# Power_Distro_Board_V5.net
KiCad netlist of a schematic drawn in EAGLE
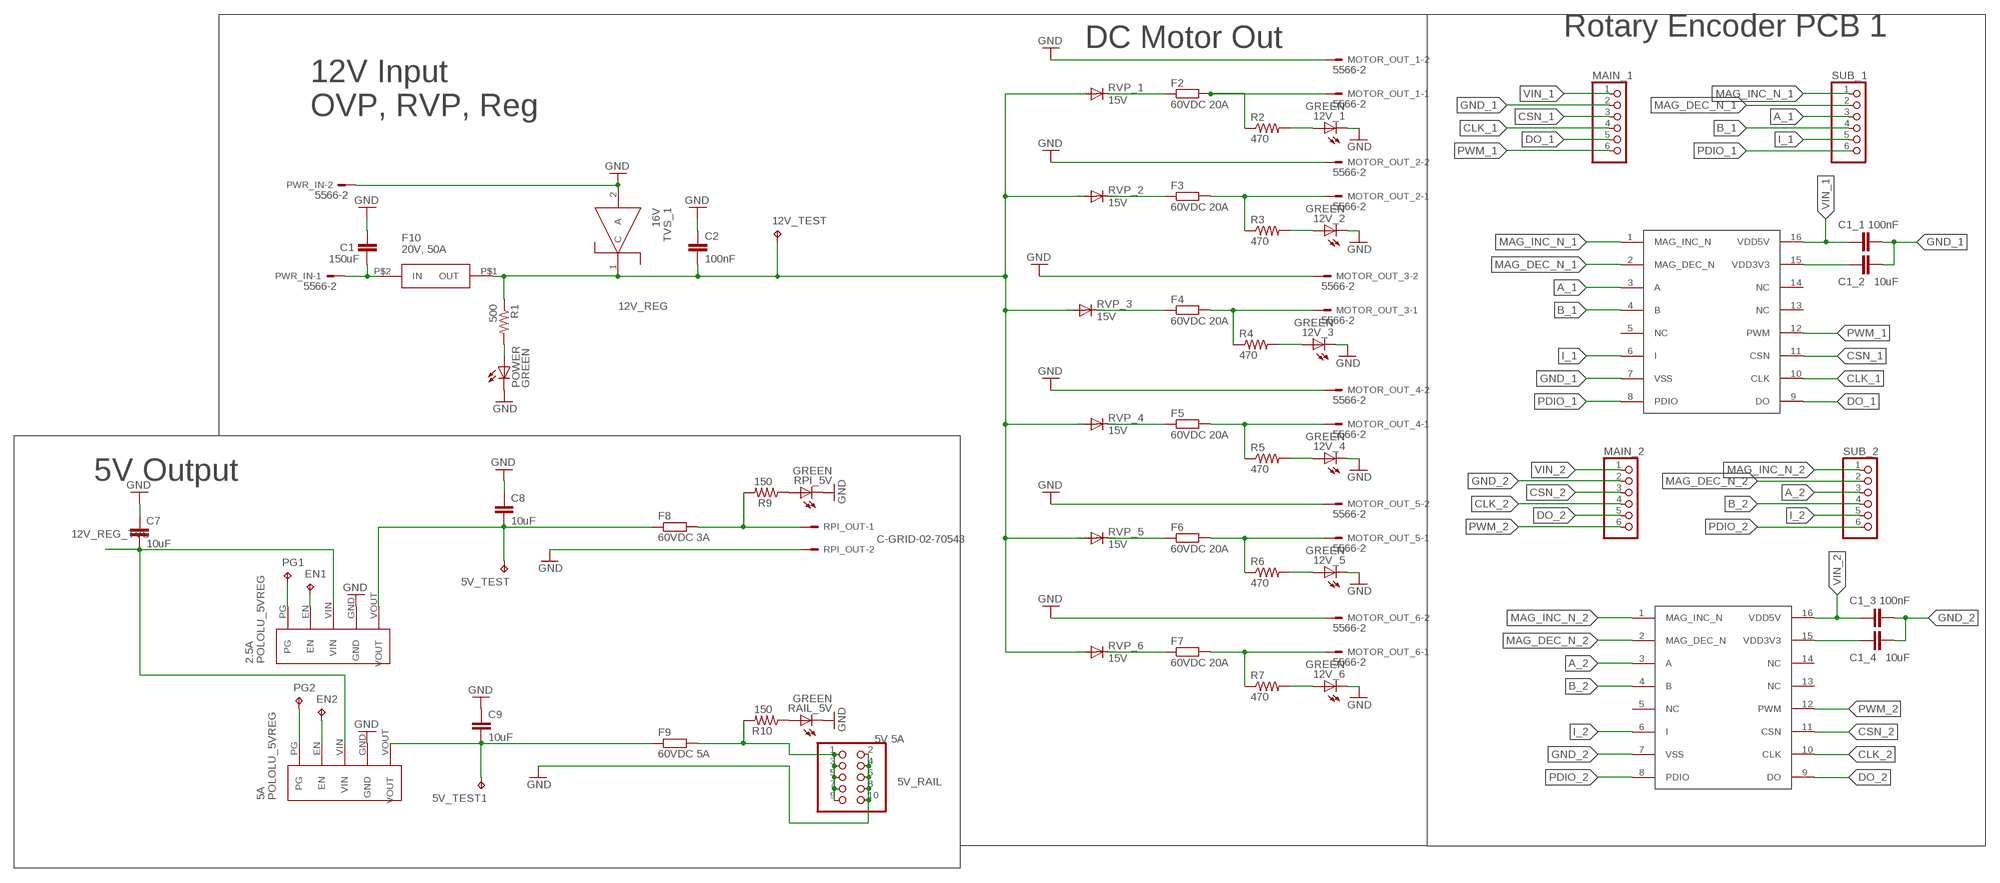
[diagram p0: schematic, sheet 1]

(export (version "E")
  (design (tool "Eeschema 10.0.6"))
  (components
    (comp (ref "2.5A")
      (value "POLOLU_5VREG")
      (footprint "eagle-import:SIP5")
      (libsource (lib "eagle-import") (part "POLOLU_5VREG"))
    )
    (comp (ref "5A")
      (value "POLOLU_5VREG")
      (footprint "eagle-import:SIP5")
      (libsource (lib "eagle-import") (part "POLOLU_5VREG"))
    )
    (comp (ref "5V_RAIL")
      (value "5V 5A")
      (footprint "eagle-import:2X05")
      (libsource (lib "eagle-import") (part "PINHD-2X5"))
    )
    (comp (ref "5V_TEST")
      (value "TPPAD1-13")
      (footprint "eagle-import:P1-13")
      (libsource (lib "eagle-import") (part "TPPAD1-13"))
    )
    (comp (ref "5V_TEST1")
      (value "TPPAD1-13")
      (footprint "eagle-import:P1-13")
      (libsource (lib "eagle-import") (part "TPPAD1-13"))
    )
    (comp (ref "12V_1")
      (value "GREEN")
      (footprint "eagle-import:SML1206")
      (libsource (lib "eagle-import") (part "LEDSML1206"))
    )
    (comp (ref "12V_2")
      (value "GREEN")
      (footprint "eagle-import:SML1206")
      (libsource (lib "eagle-import") (part "LEDSML1206"))
    )
    (comp (ref "12V_3")
      (value "GREEN")
      (footprint "eagle-import:SML1206")
      (libsource (lib "eagle-import") (part "LEDSML1206"))
    )
    (comp (ref "12V_4")
      (value "GREEN")
      (footprint "eagle-import:SML1206")
      (libsource (lib "eagle-import") (part "LEDSML1206"))
    )
    (comp (ref "12V_5")
      (value "GREEN")
      (footprint "eagle-import:SML1206")
      (libsource (lib "eagle-import") (part "LEDSML1206"))
    )
    (comp (ref "12V_6")
      (value "GREEN")
      (footprint "eagle-import:SML1206")
      (libsource (lib "eagle-import") (part "LEDSML1206"))
    )
    (comp (ref "12V_TEST")
      (value "TPPAD1-13")
      (footprint "eagle-import:P1-13")
      (libsource (lib "eagle-import") (part "TPPAD1-13"))
    )
    (comp (ref "C1")
      (value "150uF")
      (footprint "eagle-import:C1206")
      (libsource (lib "eagle-import") (part "C-EUC1206"))
    )
    (comp (ref "C1_1")
      (value "100nF")
      (footprint "eagle-import:C1206")
      (libsource (lib "eagle-import") (part "C-EUC1206"))
    )
    (comp (ref "C1_2")
      (value "10uF")
      (footprint "eagle-import:C1206")
      (libsource (lib "eagle-import") (part "C-EUC1206"))
    )
    (comp (ref "C1_3")
      (value "100nF")
      (footprint "eagle-import:C1206")
      (libsource (lib "eagle-import") (part "C-EUC1206"))
    )
    (comp (ref "C1_4")
      (value "10uF")
      (footprint "eagle-import:C1206")
      (libsource (lib "eagle-import") (part "C-EUC1206"))
    )
    (comp (ref "C2")
      (value "100nF")
      (footprint "eagle-import:C1206")
      (libsource (lib "eagle-import") (part "C-EUC1206"))
    )
    (comp (ref "C7")
      (value "10uF")
      (footprint "eagle-import:C1206")
      (libsource (lib "eagle-import") (part "C-EUC1206"))
    )
    (comp (ref "C8")
      (value "10uF")
      (footprint "eagle-import:C1206")
      (libsource (lib "eagle-import") (part "C-EUC1206"))
    )
    (comp (ref "C9")
      (value "10uF")
      (footprint "eagle-import:C1206")
      (libsource (lib "eagle-import") (part "C-EUC1206"))
    )
    (comp (ref "EN1")
      (value "TPPAD1-13")
      (footprint "eagle-import:P1-13")
      (libsource (lib "eagle-import") (part "TPPAD1-13"))
    )
    (comp (ref "EN2")
      (value "TPPAD1-13")
      (footprint "eagle-import:P1-13")
      (libsource (lib "eagle-import") (part "TPPAD1-13"))
    )
    (comp (ref "ENC_1")
      (value "ENCODER_AS5045B")
      (footprint "eagle-import:SSOP16")
      (libsource (lib "eagle-import") (part "ENCODER_AS5045B"))
    )
    (comp (ref "ENC_2")
      (value "ENCODER_AS5045B")
      (footprint "eagle-import:SSOP16")
      (libsource (lib "eagle-import") (part "ENCODER_AS5045B"))
    )
    (comp (ref "F2")
      (value "60VDC 20A")
      (footprint "eagle-import:M1206")
      (libsource (lib "eagle-import") (part "R-EU_M1206"))
    )
    (comp (ref "F3")
      (value "60VDC 20A")
      (footprint "eagle-import:M1206")
      (libsource (lib "eagle-import") (part "R-EU_M1206"))
    )
    (comp (ref "F4")
      (value "60VDC 20A")
      (footprint "eagle-import:M1206")
      (libsource (lib "eagle-import") (part "R-EU_M1206"))
    )
    (comp (ref "F5")
      (value "60VDC 20A")
      (footprint "eagle-import:M1206")
      (libsource (lib "eagle-import") (part "R-EU_M1206"))
    )
    (comp (ref "F6")
      (value "60VDC 20A")
      (footprint "eagle-import:M1206")
      (libsource (lib "eagle-import") (part "R-EU_M1206"))
    )
    (comp (ref "F7")
      (value "60VDC 20A")
      (footprint "eagle-import:M1206")
      (libsource (lib "eagle-import") (part "R-EU_M1206"))
    )
    (comp (ref "F8")
      (value "60VDC 3A")
      (footprint "eagle-import:M1206")
      (libsource (lib "eagle-import") (part "R-EU_M1206"))
    )
    (comp (ref "F9")
      (value "60VDC 5A")
      (footprint "eagle-import:M1206")
      (libsource (lib "eagle-import") (part "R-EU_M1206"))
    )
    (comp (ref "F10")
      (value "20V, 50A")
      (footprint "eagle-import:NANO")
      (libsource (lib "eagle-import") (part "LITTLEFUSE_NANO"))
    )
    (comp (ref "MAIN_1")
      (value "PINHD-1X6")
      (footprint "eagle-import:1X06")
      (libsource (lib "eagle-import") (part "PINHD-1X6"))
    )
    (comp (ref "MAIN_2")
      (value "PINHD-1X6")
      (footprint "eagle-import:1X06")
      (libsource (lib "eagle-import") (part "PINHD-1X6"))
    )
    (comp (ref "MOTOR_OUT_1")
      (value "5566-2")
      (footprint "eagle-import:5566-2")
      (libsource (lib "eagle-import") (part "5566-2"))
    )
    (comp (ref "MOTOR_OUT_2")
      (value "5566-2")
      (footprint "eagle-import:5566-2")
      (libsource (lib "eagle-import") (part "5566-2"))
    )
    (comp (ref "MOTOR_OUT_3")
      (value "5566-2")
      (footprint "eagle-import:5566-2")
      (libsource (lib "eagle-import") (part "5566-2"))
    )
    (comp (ref "MOTOR_OUT_4")
      (value "5566-2")
      (footprint "eagle-import:5566-2")
      (libsource (lib "eagle-import") (part "5566-2"))
    )
    (comp (ref "MOTOR_OUT_5")
      (value "5566-2")
      (footprint "eagle-import:5566-2")
      (libsource (lib "eagle-import") (part "5566-2"))
    )
    (comp (ref "MOTOR_OUT_6")
      (value "5566-2")
      (footprint "eagle-import:5566-2")
      (libsource (lib "eagle-import") (part "5566-2"))
    )
    (comp (ref "PG1")
      (value "TPPAD1-13")
      (footprint "eagle-import:P1-13")
      (libsource (lib "eagle-import") (part "TPPAD1-13"))
    )
    (comp (ref "PG2")
      (value "TPPAD1-13")
      (footprint "eagle-import:P1-13")
      (libsource (lib "eagle-import") (part "TPPAD1-13"))
    )
    (comp (ref "POWER")
      (value "GREEN")
      (footprint "eagle-import:SML1206")
      (libsource (lib "eagle-import") (part "LEDSML1206"))
    )
    (comp (ref "PWR_IN")
      (value "5566-2")
      (footprint "eagle-import:5566-2")
      (libsource (lib "eagle-import") (part "5566-2"))
    )
    (comp (ref "R1")
      (value "500")
      (footprint "eagle-import:R1206")
      (libsource (lib "eagle-import") (part "R-US_R1206"))
    )
    (comp (ref "R2")
      (value "470")
      (footprint "eagle-import:R1206")
      (libsource (lib "eagle-import") (part "R-US_R1206"))
    )
    (comp (ref "R3")
      (value "470")
      (footprint "eagle-import:R1206")
      (libsource (lib "eagle-import") (part "R-US_R1206"))
    )
    (comp (ref "R4")
      (value "470")
      (footprint "eagle-import:R1206")
      (libsource (lib "eagle-import") (part "R-US_R1206"))
    )
    (comp (ref "R5")
      (value "470")
      (footprint "eagle-import:R1206")
      (libsource (lib "eagle-import") (part "R-US_R1206"))
    )
    (comp (ref "R6")
      (value "470")
      (footprint "eagle-import:R1206")
      (libsource (lib "eagle-import") (part "R-US_R1206"))
    )
    (comp (ref "R7")
      (value "470")
      (footprint "eagle-import:R1206")
      (libsource (lib "eagle-import") (part "R-US_R1206"))
    )
    (comp (ref "R9")
      (value "150")
      (footprint "eagle-import:R1206")
      (libsource (lib "eagle-import") (part "R-US_R1206"))
    )
    (comp (ref "R10")
      (value "150")
      (footprint "eagle-import:R1206")
      (libsource (lib "eagle-import") (part "R-US_R1206"))
    )
    (comp (ref "RAIL_5V")
      (value "GREEN")
      (footprint "eagle-import:SML1206")
      (libsource (lib "eagle-import") (part "LEDSML1206"))
    )
    (comp (ref "RPI_5V")
      (value "GREEN")
      (footprint "eagle-import:SML1206")
      (libsource (lib "eagle-import") (part "LEDSML1206"))
    )
    (comp (ref "RPI_OUT")
      (value "C-GRID-02-70543")
      (footprint "eagle-import:70543-02")
      (libsource (lib "eagle-import") (part "C-GRID-02-70543"))
    )
    (comp (ref "RVP_1")
      (value "15V")
      (footprint "eagle-import:TO220ACS")
      (libsource (lib "eagle-import") (part "BYT08P"))
    )
    (comp (ref "RVP_2")
      (value "15V")
      (footprint "eagle-import:TO220ACS")
      (libsource (lib "eagle-import") (part "BYT08P"))
    )
    (comp (ref "RVP_3")
      (value "15V")
      (footprint "eagle-import:TO220ACS")
      (libsource (lib "eagle-import") (part "BYT08P"))
    )
    (comp (ref "RVP_4")
      (value "15V")
      (footprint "eagle-import:TO220ACS")
      (libsource (lib "eagle-import") (part "BYT08P"))
    )
    (comp (ref "RVP_5")
      (value "15V")
      (footprint "eagle-import:TO220ACS")
      (libsource (lib "eagle-import") (part "BYT08P"))
    )
    (comp (ref "RVP_6")
      (value "15V")
      (footprint "eagle-import:TO220ACS")
      (libsource (lib "eagle-import") (part "BYT08P"))
    )
    (comp (ref "SUB_1")
      (value "PINHD-1X6")
      (footprint "eagle-import:1X06")
      (libsource (lib "eagle-import") (part "PINHD-1X6"))
    )
    (comp (ref "SUB_2")
      (value "PINHD-1X6")
      (footprint "eagle-import:1X06")
      (libsource (lib "eagle-import") (part "PINHD-1X6"))
    )
    (comp (ref "TVS_1")
      (value "16V")
      (footprint "eagle-import:DO-214AC")
      (libsource (lib "eagle-import") (part "SMAJ26A_TVSSMA"))
    )
  )
  (nets
    (net (code "1") (name "/12V_REG") (class "Default")
      (node (ref "12V_TEST") (pin "TP") (pinfunction "TP_TP") (pintype "input"))
      (node (ref "C2") (pin "2") (pinfunction "2_2") (pintype "passive"))
      (node (ref "F10") (pin "P$1") (pinfunction "OUT_P$1") (pintype "bidirectional"))
      (node (ref "R1") (pin "1") (pinfunction "1_1") (pintype "passive"))
      (node (ref "RVP_1") (pin "A") (pinfunction "A_A") (pintype "passive"))
      (node (ref "RVP_2") (pin "A") (pinfunction "A_A") (pintype "passive"))
      (node (ref "RVP_3") (pin "A") (pinfunction "A_A") (pintype "passive"))
      (node (ref "RVP_4") (pin "A") (pinfunction "A_A") (pintype "passive"))
      (node (ref "RVP_5") (pin "A") (pinfunction "A_A") (pintype "passive"))
      (node (ref "RVP_6") (pin "A") (pinfunction "A_A") (pintype "passive"))
      (node (ref "TVS_1") (pin "1") (pinfunction "C_1") (pintype "bidirectional"))
    )
    (net (code "2") (name "/12V_REG_TVS") (class "Default")
      (node (ref "2.5A") (pin "VIN") (pinfunction "VIN_VIN") (pintype "bidirectional"))
      (node (ref "5A") (pin "VIN") (pinfunction "VIN_VIN") (pintype "bidirectional"))
      (node (ref "C7") (pin "2") (pinfunction "2_2") (pintype "passive"))
    )
    (net (code "3") (name "A_1") (class "Default")
      (node (ref "ENC_1") (pin "3") (pinfunction "A_3") (pintype "bidirectional"))
      (node (ref "SUB_1") (pin "3") (pinfunction "3_3") (pintype "passive"))
    )
    (net (code "4") (name "A_2") (class "Default")
      (node (ref "ENC_2") (pin "3") (pinfunction "A_3") (pintype "bidirectional"))
      (node (ref "SUB_2") (pin "3") (pinfunction "3_3") (pintype "passive"))
    )
    (net (code "5") (name "B_1") (class "Default")
      (node (ref "ENC_1") (pin "4") (pinfunction "B_4") (pintype "bidirectional"))
      (node (ref "SUB_1") (pin "4") (pinfunction "4_4") (pintype "passive"))
    )
    (net (code "6") (name "B_2") (class "Default")
      (node (ref "ENC_2") (pin "4") (pinfunction "B_4") (pintype "bidirectional"))
      (node (ref "SUB_2") (pin "4") (pinfunction "4_4") (pintype "passive"))
    )
    (net (code "7") (name "CLK_1") (class "Default")
      (node (ref "ENC_1") (pin "10") (pinfunction "CLK_10") (pintype "bidirectional"))
      (node (ref "MAIN_1") (pin "4") (pinfunction "4_4") (pintype "passive"))
    )
    (net (code "8") (name "CLK_2") (class "Default")
      (node (ref "ENC_2") (pin "10") (pinfunction "CLK_10") (pintype "bidirectional"))
      (node (ref "MAIN_2") (pin "4") (pinfunction "4_4") (pintype "passive"))
    )
    (net (code "9") (name "CSN_1") (class "Default")
      (node (ref "ENC_1") (pin "11") (pinfunction "CSN_11") (pintype "bidirectional"))
      (node (ref "MAIN_1") (pin "3") (pinfunction "3_3") (pintype "passive"))
    )
    (net (code "10") (name "CSN_2") (class "Default")
      (node (ref "ENC_2") (pin "11") (pinfunction "CSN_11") (pintype "bidirectional"))
      (node (ref "MAIN_2") (pin "3") (pinfunction "3_3") (pintype "passive"))
    )
    (net (code "11") (name "DO_1") (class "Default")
      (node (ref "ENC_1") (pin "9") (pinfunction "DO_9") (pintype "bidirectional"))
      (node (ref "MAIN_1") (pin "5") (pinfunction "5_5") (pintype "passive"))
    )
    (net (code "12") (name "DO_2") (class "Default")
      (node (ref "ENC_2") (pin "9") (pinfunction "DO_9") (pintype "bidirectional"))
      (node (ref "MAIN_2") (pin "5") (pinfunction "5_5") (pintype "passive"))
    )
    (net (code "13") (name "GND") (class "Default")
      (node (ref "12V_1") (pin "C") (pinfunction "C_C") (pintype "passive"))
      (node (ref "12V_2") (pin "C") (pinfunction "C_C") (pintype "passive"))
      (node (ref "12V_3") (pin "C") (pinfunction "C_C") (pintype "passive"))
      (node (ref "12V_4") (pin "C") (pinfunction "C_C") (pintype "passive"))
      (node (ref "12V_5") (pin "C") (pinfunction "C_C") (pintype "passive"))
      (node (ref "12V_6") (pin "C") (pinfunction "C_C") (pintype "passive"))
      (node (ref "2.5A") (pin "GND") (pinfunction "GND_GND") (pintype "bidirectional"))
      (node (ref "5A") (pin "GND") (pinfunction "GND_GND") (pintype "bidirectional"))
      (node (ref "5V_RAIL") (pin "10") (pinfunction "10_10") (pintype "passive"))
      (node (ref "5V_RAIL") (pin "2") (pinfunction "2_2") (pintype "passive"))
      (node (ref "5V_RAIL") (pin "4") (pinfunction "4_4") (pintype "passive"))
      (node (ref "5V_RAIL") (pin "6") (pinfunction "6_6") (pintype "passive"))
      (node (ref "5V_RAIL") (pin "8") (pinfunction "8_8") (pintype "passive"))
      (node (ref "C1") (pin "1") (pinfunction "1_1") (pintype "passive"))
      (node (ref "C2") (pin "1") (pinfunction "1_1") (pintype "passive"))
      (node (ref "C7") (pin "1") (pinfunction "1_1") (pintype "passive"))
      (node (ref "C8") (pin "1") (pinfunction "1_1") (pintype "passive"))
      (node (ref "C9") (pin "1") (pinfunction "1_1") (pintype "passive"))
      (node (ref "MOTOR_OUT_1") (pin "2") (pinfunction "S_2") (pintype "passive"))
      (node (ref "MOTOR_OUT_2") (pin "2") (pinfunction "S_2") (pintype "passive"))
      (node (ref "MOTOR_OUT_3") (pin "2") (pinfunction "S_2") (pintype "passive"))
      (node (ref "MOTOR_OUT_4") (pin "2") (pinfunction "S_2") (pintype "passive"))
      (node (ref "MOTOR_OUT_5") (pin "2") (pinfunction "S_2") (pintype "passive"))
      (node (ref "MOTOR_OUT_6") (pin "2") (pinfunction "S_2") (pintype "passive"))
      (node (ref "POWER") (pin "C") (pinfunction "C_C") (pintype "passive"))
      (node (ref "PWR_IN") (pin "2") (pinfunction "S_2") (pintype "passive"))
      (node (ref "RAIL_5V") (pin "C") (pinfunction "C_C") (pintype "passive"))
      (node (ref "RPI_5V") (pin "C") (pinfunction "C_C") (pintype "passive"))
      (node (ref "RPI_OUT") (pin "2") (pinfunction "S_2") (pintype "passive"))
      (node (ref "TVS_1") (pin "2") (pinfunction "A_2") (pintype "bidirectional"))
    )
    (net (code "14") (name "GND_1") (class "Default")
      (node (ref "C1_1") (pin "2") (pinfunction "2_2") (pintype "passive"))
      (node (ref "C1_2") (pin "2") (pinfunction "2_2") (pintype "passive"))
      (node (ref "ENC_1") (pin "7") (pinfunction "VSS_7") (pintype "bidirectional"))
      (node (ref "MAIN_1") (pin "2") (pinfunction "2_2") (pintype "passive"))
    )
    (net (code "15") (name "GND_2") (class "Default")
      (node (ref "C1_3") (pin "2") (pinfunction "2_2") (pintype "passive"))
      (node (ref "C1_4") (pin "2") (pinfunction "2_2") (pintype "passive"))
      (node (ref "ENC_2") (pin "7") (pinfunction "VSS_7") (pintype "bidirectional"))
      (node (ref "MAIN_2") (pin "2") (pinfunction "2_2") (pintype "passive"))
    )
    (net (code "16") (name "I_1") (class "Default")
      (node (ref "ENC_1") (pin "6") (pinfunction "I_6") (pintype "bidirectional"))
      (node (ref "SUB_1") (pin "5") (pinfunction "5_5") (pintype "passive"))
    )
    (net (code "17") (name "I_2") (class "Default")
      (node (ref "ENC_2") (pin "6") (pinfunction "I_6") (pintype "bidirectional"))
      (node (ref "SUB_2") (pin "5") (pinfunction "5_5") (pintype "passive"))
    )
    (net (code "18") (name "MAG_DEC_N_1") (class "Default")
      (node (ref "ENC_1") (pin "2") (pinfunction "MAG_DEC_N_2") (pintype "bidirectional"))
      (node (ref "SUB_1") (pin "2") (pinfunction "2_2") (pintype "passive"))
    )
    (net (code "19") (name "MAG_DEC_N_2") (class "Default")
      (node (ref "ENC_2") (pin "2") (pinfunction "MAG_DEC_N_2") (pintype "bidirectional"))
      (node (ref "SUB_2") (pin "2") (pinfunction "2_2") (pintype "passive"))
    )
    (net (code "20") (name "MAG_INC_N_1") (class "Default")
      (node (ref "ENC_1") (pin "1") (pinfunction "MAG_INC_N_1") (pintype "bidirectional"))
      (node (ref "SUB_1") (pin "1") (pinfunction "1_1") (pintype "passive"))
    )
    (net (code "21") (name "MAG_INC_N_2") (class "Default")
      (node (ref "ENC_2") (pin "1") (pinfunction "MAG_INC_N_1") (pintype "bidirectional"))
      (node (ref "SUB_2") (pin "1") (pinfunction "1_1") (pintype "passive"))
    )
    (net (code "22") (name "Net-(2.5A-PadEN)") (class "Default")
      (node (ref "2.5A") (pin "EN") (pinfunction "EN_EN") (pintype "bidirectional"))
      (node (ref "EN1") (pin "TP") (pinfunction "TP_TP") (pintype "input"))
    )
    (net (code "23") (name "Net-(2.5A-PadPG)") (class "Default")
      (node (ref "2.5A") (pin "PG") (pinfunction "PG_PG") (pintype "bidirectional"))
      (node (ref "PG1") (pin "TP") (pinfunction "TP_TP") (pintype "input"))
    )
    (net (code "24") (name "Net-(2.5A-PadVOUT)") (class "Default")
      (node (ref "2.5A") (pin "VOUT") (pinfunction "VOUT_VOUT") (pintype "bidirectional"))
      (node (ref "5V_TEST") (pin "TP") (pinfunction "TP_TP") (pintype "input"))
      (node (ref "C8") (pin "2") (pinfunction "2_2") (pintype "passive"))
      (node (ref "F8") (pin "1") (pinfunction "1_1") (pintype "passive"))
    )
    (net (code "25") (name "Net-(5A-PadEN)") (class "Default")
      (node (ref "5A") (pin "EN") (pinfunction "EN_EN") (pintype "bidirectional"))
      (node (ref "EN2") (pin "TP") (pinfunction "TP_TP") (pintype "input"))
    )
    (net (code "26") (name "Net-(5A-PadPG)") (class "Default")
      (node (ref "5A") (pin "PG") (pinfunction "PG_PG") (pintype "bidirectional"))
      (node (ref "PG2") (pin "TP") (pinfunction "TP_TP") (pintype "input"))
    )
    (net (code "27") (name "Net-(5A-PadVOUT)") (class "Default")
      (node (ref "5A") (pin "VOUT") (pinfunction "VOUT_VOUT") (pintype "bidirectional"))
      (node (ref "5V_TEST1") (pin "TP") (pinfunction "TP_TP") (pintype "input"))
      (node (ref "C9") (pin "2") (pinfunction "2_2") (pintype "passive"))
      (node (ref "F9") (pin "1") (pinfunction "1_1") (pintype "passive"))
    )
    (net (code "28") (name "Net-(5V_RAIL-Pad1)") (class "Default")
      (node (ref "5V_RAIL") (pin "1") (pinfunction "1_1") (pintype "passive"))
      (node (ref "5V_RAIL") (pin "3") (pinfunction "3_3") (pintype "passive"))
      (node (ref "5V_RAIL") (pin "5") (pinfunction "5_5") (pintype "passive"))
      (node (ref "5V_RAIL") (pin "7") (pinfunction "7_7") (pintype "passive"))
      (node (ref "5V_RAIL") (pin "9") (pinfunction "9_9") (pintype "passive"))
      (node (ref "F9") (pin "2") (pinfunction "2_2") (pintype "passive"))
      (node (ref "R10") (pin "2") (pinfunction "2_2") (pintype "passive"))
    )
    (net (code "29") (name "Net-(12V_1-PadA)") (class "Default")
      (node (ref "12V_1") (pin "A") (pinfunction "A_A") (pintype "passive"))
      (node (ref "R2") (pin "2") (pinfunction "2_2") (pintype "passive"))
    )
    (net (code "30") (name "Net-(12V_2-PadA)") (class "Default")
      (node (ref "12V_2") (pin "A") (pinfunction "A_A") (pintype "passive"))
      (node (ref "R3") (pin "2") (pinfunction "2_2") (pintype "passive"))
    )
    (net (code "31") (name "Net-(12V_3-PadA)") (class "Default")
      (node (ref "12V_3") (pin "A") (pinfunction "A_A") (pintype "passive"))
      (node (ref "R4") (pin "2") (pinfunction "2_2") (pintype "passive"))
    )
    (net (code "32") (name "Net-(12V_4-PadA)") (class "Default")
      (node (ref "12V_4") (pin "A") (pinfunction "A_A") (pintype "passive"))
      (node (ref "R5") (pin "2") (pinfunction "2_2") (pintype "passive"))
    )
    (net (code "33") (name "Net-(12V_5-PadA)") (class "Default")
      (node (ref "12V_5") (pin "A") (pinfunction "A_A") (pintype "passive"))
      (node (ref "R6") (pin "2") (pinfunction "2_2") (pintype "passive"))
    )
    (net (code "34") (name "Net-(12V_6-PadA)") (class "Default")
      (node (ref "12V_6") (pin "A") (pinfunction "A_A") (pintype "passive"))
      (node (ref "R7") (pin "2") (pinfunction "2_2") (pintype "passive"))
    )
    (net (code "35") (name "Net-(ENC_1-VDD3V3)") (class "Default")
      (node (ref "C1_2") (pin "1") (pinfunction "1_1") (pintype "passive"))
      (node (ref "ENC_1") (pin "15") (pinfunction "VDD3V3_15") (pintype "bidirectional"))
    )
    (net (code "36") (name "Net-(ENC_2-VDD3V3)") (class "Default")
      (node (ref "C1_4") (pin "1") (pinfunction "1_1") (pintype "passive"))
      (node (ref "ENC_2") (pin "15") (pinfunction "VDD3V3_15") (pintype "bidirectional"))
    )
    (net (code "37") (name "Net-(F2-Pad1)") (class "Default")
      (node (ref "F2") (pin "1") (pinfunction "1_1") (pintype "passive"))
      (node (ref "RVP_1") (pin "C") (pinfunction "C_C") (pintype "passive"))
    )
    (net (code "38") (name "Net-(F3-Pad1)") (class "Default")
      (node (ref "F3") (pin "1") (pinfunction "1_1") (pintype "passive"))
      (node (ref "RVP_2") (pin "C") (pinfunction "C_C") (pintype "passive"))
    )
    (net (code "39") (name "Net-(F4-Pad1)") (class "Default")
      (node (ref "F4") (pin "1") (pinfunction "1_1") (pintype "passive"))
      (node (ref "RVP_3") (pin "C") (pinfunction "C_C") (pintype "passive"))
    )
    (net (code "40") (name "Net-(F5-Pad1)") (class "Default")
      (node (ref "F5") (pin "1") (pinfunction "1_1") (pintype "passive"))
      (node (ref "RVP_4") (pin "C") (pinfunction "C_C") (pintype "passive"))
    )
    (net (code "41") (name "Net-(F6-Pad1)") (class "Default")
      (node (ref "F6") (pin "1") (pinfunction "1_1") (pintype "passive"))
      (node (ref "RVP_5") (pin "C") (pinfunction "C_C") (pintype "passive"))
    )
    (net (code "42") (name "Net-(F7-Pad1)") (class "Default")
      (node (ref "F7") (pin "1") (pinfunction "1_1") (pintype "passive"))
      (node (ref "RVP_6") (pin "C") (pinfunction "C_C") (pintype "passive"))
    )
    (net (code "43") (name "Net-(F10-IN)") (class "Default")
      (node (ref "C1") (pin "2") (pinfunction "2_2") (pintype "passive"))
      (node (ref "F10") (pin "P$2") (pinfunction "IN_P$2") (pintype "bidirectional"))
      (node (ref "PWR_IN") (pin "1") (pinfunction "S_1") (pintype "passive"))
    )
    (net (code "44") (name "Net-(MOTOR_OUT_1A-S)") (class "Default")
      (node (ref "F2") (pin "2") (pinfunction "2_2") (pintype "passive"))
      (node (ref "MOTOR_OUT_1") (pin "1") (pinfunction "S_1") (pintype "passive"))
      (node (ref "R2") (pin "1") (pinfunction "1_1") (pintype "passive"))
    )
    (net (code "45") (name "Net-(MOTOR_OUT_2A-S)") (class "Default")
      (node (ref "F3") (pin "2") (pinfunction "2_2") (pintype "passive"))
      (node (ref "MOTOR_OUT_2") (pin "1") (pinfunction "S_1") (pintype "passive"))
      (node (ref "R3") (pin "1") (pinfunction "1_1") (pintype "passive"))
    )
    (net (code "46") (name "Net-(MOTOR_OUT_3A-S)") (class "Default")
      (node (ref "F4") (pin "2") (pinfunction "2_2") (pintype "passive"))
      (node (ref "MOTOR_OUT_3") (pin "1") (pinfunction "S_1") (pintype "passive"))
      (node (ref "R4") (pin "1") (pinfunction "1_1") (pintype "passive"))
    )
    (net (code "47") (name "Net-(MOTOR_OUT_4A-S)") (class "Default")
      (node (ref "F5") (pin "2") (pinfunction "2_2") (pintype "passive"))
      (node (ref "MOTOR_OUT_4") (pin "1") (pinfunction "S_1") (pintype "passive"))
      (node (ref "R5") (pin "1") (pinfunction "1_1") (pintype "passive"))
    )
    (net (code "48") (name "Net-(MOTOR_OUT_5A-S)") (class "Default")
      (node (ref "F6") (pin "2") (pinfunction "2_2") (pintype "passive"))
      (node (ref "MOTOR_OUT_5") (pin "1") (pinfunction "S_1") (pintype "passive"))
      (node (ref "R6") (pin "1") (pinfunction "1_1") (pintype "passive"))
    )
    (net (code "49") (name "Net-(MOTOR_OUT_6A-S)") (class "Default")
      (node (ref "F7") (pin "2") (pinfunction "2_2") (pintype "passive"))
      (node (ref "MOTOR_OUT_6") (pin "1") (pinfunction "S_1") (pintype "passive"))
      (node (ref "R7") (pin "1") (pinfunction "1_1") (pintype "passive"))
    )
    (net (code "50") (name "Net-(POWER-PadA)") (class "Default")
      (node (ref "POWER") (pin "A") (pinfunction "A_A") (pintype "passive"))
      (node (ref "R1") (pin "2") (pinfunction "2_2") (pintype "passive"))
    )
    (net (code "51") (name "Net-(R9-Pad1)") (class "Default")
      (node (ref "R9") (pin "1") (pinfunction "1_1") (pintype "passive"))
      (node (ref "RPI_5V") (pin "A") (pinfunction "A_A") (pintype "passive"))
    )
    (net (code "52") (name "Net-(R10-Pad1)") (class "Default")
      (node (ref "R10") (pin "1") (pinfunction "1_1") (pintype "passive"))
      (node (ref "RAIL_5V") (pin "A") (pinfunction "A_A") (pintype "passive"))
    )
    (net (code "53") (name "Net-(RPI_OUTA-S)") (class "Default")
      (node (ref "F8") (pin "2") (pinfunction "2_2") (pintype "passive"))
      (node (ref "R9") (pin "2") (pinfunction "2_2") (pintype "passive"))
      (node (ref "RPI_OUT") (pin "1") (pinfunction "S_1") (pintype "passive"))
    )
    (net (code "54") (name "PDIO_1") (class "Default")
      (node (ref "ENC_1") (pin "8") (pinfunction "PDIO_8") (pintype "bidirectional"))
      (node (ref "SUB_1") (pin "6") (pinfunction "6_6") (pintype "passive"))
    )
    (net (code "55") (name "PDIO_2") (class "Default")
      (node (ref "ENC_2") (pin "8") (pinfunction "PDIO_8") (pintype "bidirectional"))
      (node (ref "SUB_2") (pin "6") (pinfunction "6_6") (pintype "passive"))
    )
    (net (code "56") (name "PWM_1") (class "Default")
      (node (ref "ENC_1") (pin "12") (pinfunction "PWM_12") (pintype "bidirectional"))
      (node (ref "MAIN_1") (pin "6") (pinfunction "6_6") (pintype "passive"))
    )
    (net (code "57") (name "PWM_2") (class "Default")
      (node (ref "ENC_2") (pin "12") (pinfunction "PWM_12") (pintype "bidirectional"))
      (node (ref "MAIN_2") (pin "6") (pinfunction "6_6") (pintype "passive"))
    )
    (net (code "58") (name "VIN_1") (class "Default")
      (node (ref "C1_1") (pin "1") (pinfunction "1_1") (pintype "passive"))
      (node (ref "ENC_1") (pin "16") (pinfunction "VDD5V_16") (pintype "bidirectional"))
      (node (ref "MAIN_1") (pin "1") (pinfunction "1_1") (pintype "passive"))
    )
    (net (code "59") (name "VIN_2") (class "Default")
      (node (ref "C1_3") (pin "1") (pinfunction "1_1") (pintype "passive"))
      (node (ref "ENC_2") (pin "16") (pinfunction "VDD5V_16") (pintype "bidirectional"))
      (node (ref "MAIN_2") (pin "1") (pinfunction "1_1") (pintype "passive"))
    )
    (net (code "60") (name "unconnected-(ENC_1-NC-Pad5)") (class "Default")
      (node (ref "ENC_1") (pin "5") (pinfunction "NC_5") (pintype "bidirectional"))
    )
    (net (code "61") (name "unconnected-(ENC_1-NC-Pad13)") (class "Default")
      (node (ref "ENC_1") (pin "13") (pinfunction "NC_13") (pintype "bidirectional"))
    )
    (net (code "62") (name "unconnected-(ENC_1-NC-Pad14)") (class "Default")
      (node (ref "ENC_1") (pin "14") (pinfunction "NC_14") (pintype "bidirectional"))
    )
    (net (code "63") (name "unconnected-(ENC_2-NC-Pad5)") (class "Default")
      (node (ref "ENC_2") (pin "5") (pinfunction "NC_5") (pintype "bidirectional"))
    )
    (net (code "64") (name "unconnected-(ENC_2-NC-Pad13)") (class "Default")
      (node (ref "ENC_2") (pin "13") (pinfunction "NC_13") (pintype "bidirectional"))
    )
    (net (code "65") (name "unconnected-(ENC_2-NC-Pad14)") (class "Default")
      (node (ref "ENC_2") (pin "14") (pinfunction "NC_14") (pintype "bidirectional"))
    )
  )
)
